# M_C_ext_esp32_cp2102.net
KiCad netlist of a schematic drawn in EAGLE
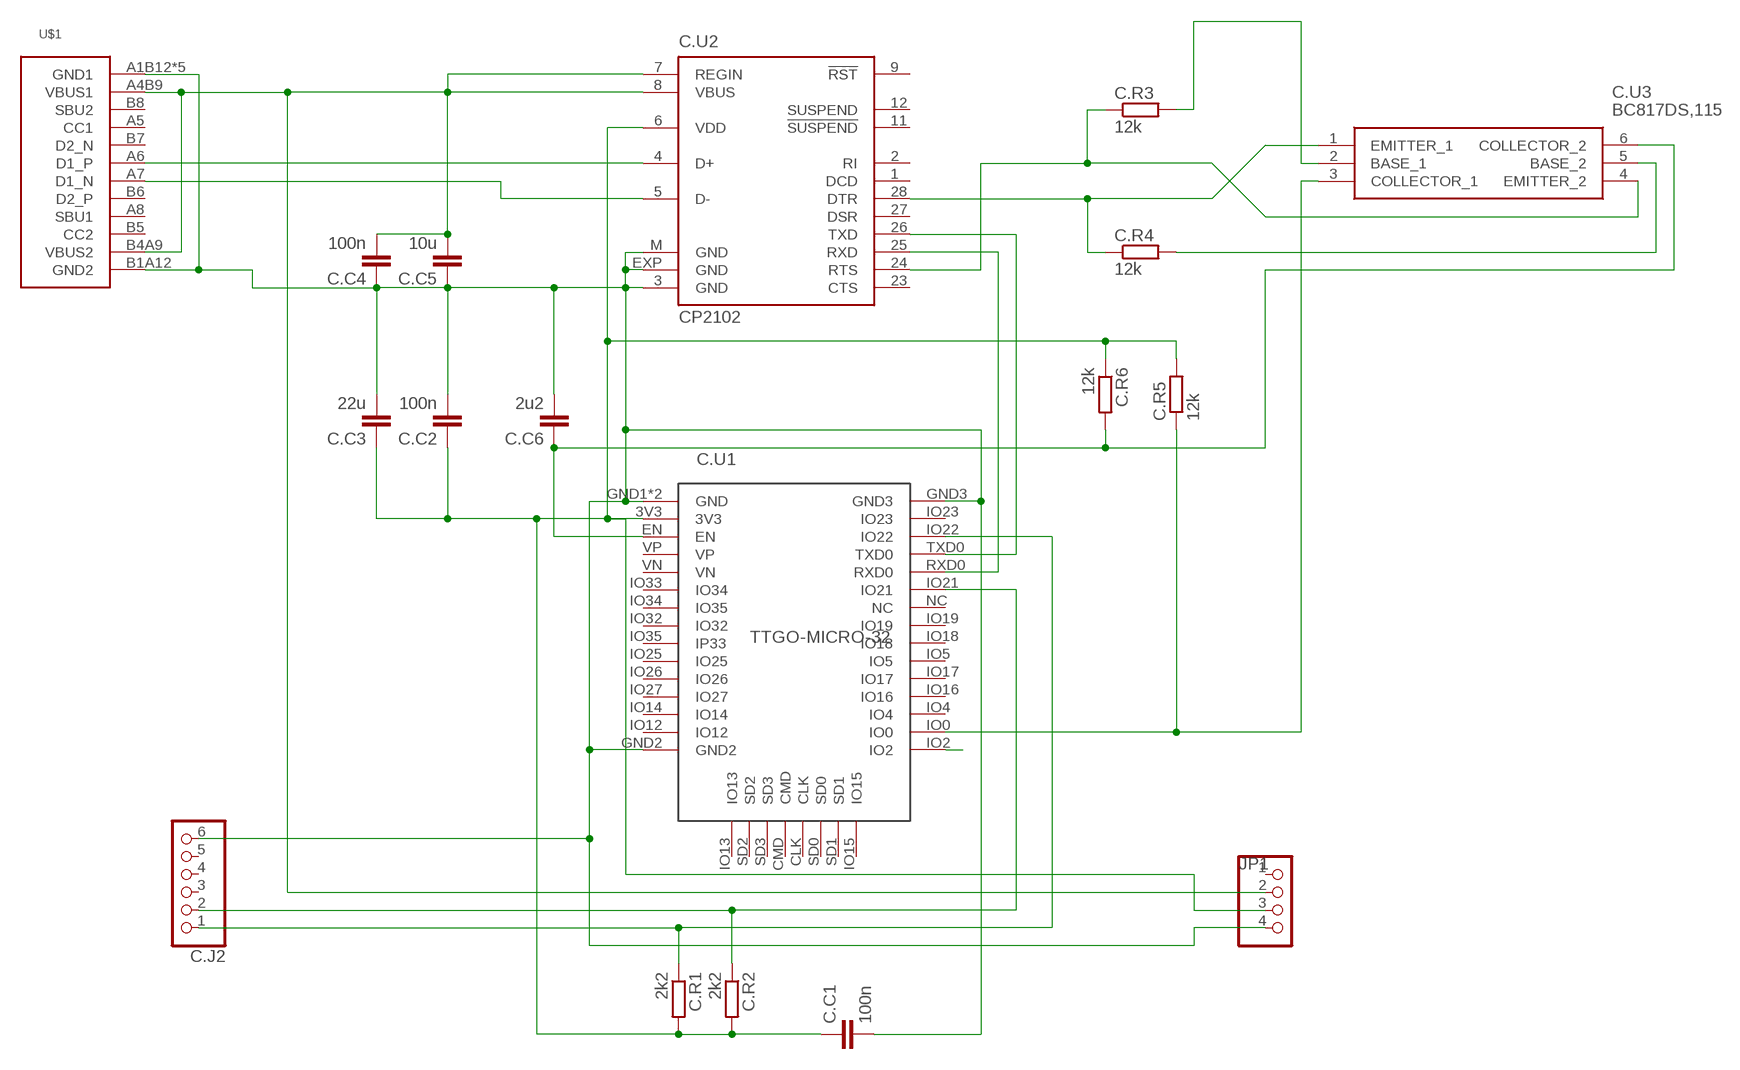
[diagram p0: schematic, sheet 1]

(export (version "E")
  (design (tool "Eeschema 10.0.6"))
  (components
    (comp (ref "C.C1")
      (value "100n")
      (footprint "eagle-import:C0603")
      (libsource (lib "eagle-import") (part "C-EUC0603"))
    )
    (comp (ref "C.C2")
      (value "100n")
      (footprint "eagle-import:C0603")
      (libsource (lib "eagle-import") (part "C-EUC0603"))
    )
    (comp (ref "C.C3")
      (value "22u")
      (footprint "eagle-import:C0805")
      (libsource (lib "eagle-import") (part "C-EUC0805"))
    )
    (comp (ref "C.C4")
      (value "100n")
      (footprint "eagle-import:C0603")
      (libsource (lib "eagle-import") (part "C-EUC0603"))
    )
    (comp (ref "C.C5")
      (value "10u")
      (footprint "eagle-import:C0603")
      (libsource (lib "eagle-import") (part "C-EUC0603"))
    )
    (comp (ref "C.C6")
      (value "2u2")
      (footprint "eagle-import:C0603")
      (libsource (lib "eagle-import") (part "C-EUC0603"))
    )
    (comp (ref "C.J2")
      (value "PINHD-1X6")
      (footprint "eagle-import:1X06")
      (libsource (lib "eagle-import") (part "PINHD-1X6"))
    )
    (comp (ref "C.R1")
      (value "2k2")
      (footprint "eagle-import:R0603")
      (libsource (lib "eagle-import") (part "R-EU_R0603"))
    )
    (comp (ref "C.R2")
      (value "2k2")
      (footprint "eagle-import:R0603")
      (libsource (lib "eagle-import") (part "R-EU_R0603"))
    )
    (comp (ref "C.R3")
      (value "12k")
      (footprint "eagle-import:R0603")
      (libsource (lib "eagle-import") (part "R-EU_R0603"))
    )
    (comp (ref "C.R4")
      (value "12k")
      (footprint "eagle-import:R0603")
      (libsource (lib "eagle-import") (part "R-EU_R0603"))
    )
    (comp (ref "C.R5")
      (value "12k")
      (footprint "eagle-import:R0603")
      (libsource (lib "eagle-import") (part "R-EU_R0603"))
    )
    (comp (ref "C.R6")
      (value "12k")
      (footprint "eagle-import:R0603")
      (libsource (lib "eagle-import") (part "R-EU_R0603"))
    )
    (comp (ref "C.U1")
      (value "TTGO-MICRO-32")
      (footprint "eagle-import:TTGO-MICRO-32")
      (libsource (lib "eagle-import") (part "TTGO-MICRO-32"))
    )
    (comp (ref "C.U2")
      (value "CP2102")
      (footprint "eagle-import:MLP28")
      (fields (field (name "MF") "FARNELL") (field (name "MPN") "CP2102-GM"))
      (libsource (lib "eagle-import") (part "CP2102"))
    )
    (comp (ref "C.U3")
      (value "BC817DS,115")
      (footprint "eagle-import:SOT95P275X110-6N")
      (fields (field (name "MOUSER_PART_NUMBER") "771-BC817DS115"))
      (libsource (lib "eagle-import") (part "BC817DS,115"))
    )
    (comp (ref "JP1")
      (value "PINHD-1X4")
      (footprint "eagle-import:1X04")
      (libsource (lib "eagle-import") (part "PINHD-1X4"))
    )
    (comp (ref "U$1")
      (value "USB-C")
      (footprint "eagle-import:USB-C")
      (libsource (lib "eagle-import") (part "USB-C"))
    )
  )
  (nets
    (net (code "1") (name "Net-(C.J2-Pad1)") (class "Default")
      (node (ref "C.J2") (pin "1") (pinfunction "1_1") (pintype "passive"))
      (node (ref "C.R1") (pin "1") (pinfunction "1_1") (pintype "passive"))
      (node (ref "C.U1") (pin "IO22") (pinfunction "IO22_IO22") (pintype "bidirectional"))
    )
    (net (code "2") (name "Net-(C.J2-Pad2)") (class "Default")
      (node (ref "C.J2") (pin "2") (pinfunction "2_2") (pintype "passive"))
      (node (ref "C.R2") (pin "1") (pinfunction "1_1") (pintype "passive"))
      (node (ref "C.U1") (pin "IO21") (pinfunction "IO21_IO21") (pintype "bidirectional"))
    )
    (net (code "3") (name "Net-(C.U2-D+)") (class "Default")
      (node (ref "C.U2") (pin "4") (pinfunction "D+_4") (pintype "bidirectional"))
      (node (ref "U$1") (pin "A6") (pinfunction "D1_P_A6") (pintype "bidirectional"))
    )
    (net (code "4") (name "Net-(C.U2-D-)") (class "Default")
      (node (ref "C.U2") (pin "5") (pinfunction "D-_5") (pintype "bidirectional"))
      (node (ref "U$1") (pin "A7") (pinfunction "D1_N_A7") (pintype "bidirectional"))
    )
    (net (code "5") (name "Net-(C.U2-DTR)") (class "Default")
      (node (ref "C.R4") (pin "1") (pinfunction "1_1") (pintype "passive"))
      (node (ref "C.U2") (pin "28") (pinfunction "DTR_28") (pintype "output"))
      (node (ref "C.U3") (pin "1") (pinfunction "EMITTER_1_1") (pintype "bidirectional"))
    )
    (net (code "6") (name "Net-(C.U2-REGIN)") (class "Default")
      (node (ref "C.C4") (pin "2") (pinfunction "2_2") (pintype "passive"))
      (node (ref "C.C5") (pin "2") (pinfunction "2_2") (pintype "passive"))
      (node (ref "C.U2") (pin "7") (pinfunction "REGIN_7") (pintype "passive"))
      (node (ref "C.U2") (pin "8") (pinfunction "VBUS_8") (pintype "input"))
      (node (ref "JP1") (pin "2") (pinfunction "2_2") (pintype "passive"))
      (node (ref "U$1") (pin "A4B9") (pinfunction "VBUS1_A4B9") (pintype "bidirectional"))
      (node (ref "U$1") (pin "B4A9") (pinfunction "VBUS2_B4A9") (pintype "bidirectional"))
    )
    (net (code "7") (name "Net-(C.U2-RTS)") (class "Default")
      (node (ref "C.R3") (pin "1") (pinfunction "1_1") (pintype "passive"))
      (node (ref "C.U2") (pin "24") (pinfunction "RTS_24") (pintype "output"))
      (node (ref "C.U3") (pin "4") (pinfunction "EMITTER_2_4") (pintype "bidirectional"))
    )
    (net (code "8") (name "Net-(C.U2-RXD)") (class "Default")
      (node (ref "C.U1") (pin "RXD0") (pinfunction "RXD0_RXD0") (pintype "bidirectional"))
      (node (ref "C.U2") (pin "25") (pinfunction "RXD_25") (pintype "input"))
    )
    (net (code "9") (name "Net-(C.U2-TXD)") (class "Default")
      (node (ref "C.U1") (pin "TXD0") (pinfunction "TXD0_TXD0") (pintype "bidirectional"))
      (node (ref "C.U2") (pin "26") (pinfunction "TXD_26") (pintype "output"))
    )
    (net (code "10") (name "Net-(C.U2-VDD)") (class "Default")
      (node (ref "C.C1") (pin "1") (pinfunction "1_1") (pintype "passive"))
      (node (ref "C.C2") (pin "1") (pinfunction "1_1") (pintype "passive"))
      (node (ref "C.C3") (pin "1") (pinfunction "1_1") (pintype "passive"))
      (node (ref "C.R1") (pin "2") (pinfunction "2_2") (pintype "passive"))
      (node (ref "C.R2") (pin "2") (pinfunction "2_2") (pintype "passive"))
      (node (ref "C.R5") (pin "2") (pinfunction "2_2") (pintype "passive"))
      (node (ref "C.R6") (pin "1") (pinfunction "1_1") (pintype "passive"))
      (node (ref "C.U1") (pin "3V3") (pinfunction "3V3_3V3") (pintype "power_in"))
      (node (ref "C.U2") (pin "6") (pinfunction "VDD_6") (pintype "power_in"))
      (node (ref "JP1") (pin "3") (pinfunction "3_3") (pintype "passive"))
    )
    (net (code "11") (name "Net-(C.U3-BASE_1)") (class "Default")
      (node (ref "C.R3") (pin "2") (pinfunction "2_2") (pintype "passive"))
      (node (ref "C.U3") (pin "2") (pinfunction "BASE_1_2") (pintype "bidirectional"))
    )
    (net (code "12") (name "Net-(C.U3-BASE_2)") (class "Default")
      (node (ref "C.R4") (pin "2") (pinfunction "2_2") (pintype "passive"))
      (node (ref "C.U3") (pin "5") (pinfunction "BASE_2_5") (pintype "bidirectional"))
    )
    (net (code "13") (name "Net-(C.U3-COLLECTOR_1)") (class "Default")
      (node (ref "C.R5") (pin "1") (pinfunction "1_1") (pintype "passive"))
      (node (ref "C.U1") (pin "IO0") (pinfunction "IO0_IO0") (pintype "bidirectional"))
      (node (ref "C.U3") (pin "3") (pinfunction "COLLECTOR_1_3") (pintype "bidirectional"))
    )
    (net (code "14") (name "Net-(C.U3-COLLECTOR_2)") (class "Default")
      (node (ref "C.C6") (pin "1") (pinfunction "1_1") (pintype "passive"))
      (node (ref "C.R6") (pin "2") (pinfunction "2_2") (pintype "passive"))
      (node (ref "C.U1") (pin "EN") (pinfunction "EN_EN") (pintype "bidirectional"))
      (node (ref "C.U3") (pin "6") (pinfunction "COLLECTOR_2_6") (pintype "bidirectional"))
    )
    (net (code "15") (name "Net-(U$1-GND2)") (class "Default")
      (node (ref "C.C1") (pin "2") (pinfunction "2_2") (pintype "passive"))
      (node (ref "C.C2") (pin "2") (pinfunction "2_2") (pintype "passive"))
      (node (ref "C.C3") (pin "2") (pinfunction "2_2") (pintype "passive"))
      (node (ref "C.C4") (pin "1") (pinfunction "1_1") (pintype "passive"))
      (node (ref "C.C5") (pin "1") (pinfunction "1_1") (pintype "passive"))
      (node (ref "C.C6") (pin "2") (pinfunction "2_2") (pintype "passive"))
      (node (ref "C.J2") (pin "6") (pinfunction "6_6") (pintype "passive"))
      (node (ref "C.U1") (pin "GND1") (pinfunction "GND_GND1") (pintype "power_in"))
      (node (ref "C.U1") (pin "GND2") (pinfunction "GND2_GND2") (pintype "power_in"))
      (node (ref "C.U1") (pin "GND3") (pinfunction "GND3_GND3") (pintype "power_in"))
      (node (ref "C.U1") (pin "GND4") (pinfunction "GND_GND4") (pintype "power_in"))
      (node (ref "C.U2") (pin "3") (pinfunction "GND_3") (pintype "power_in"))
      (node (ref "C.U2") (pin "EXP") (pinfunction "GND_EXP") (pintype "power_in"))
      (node (ref "C.U2") (pin "M") (pinfunction "GND_M") (pintype "power_in"))
      (node (ref "JP1") (pin "4") (pinfunction "4_4") (pintype "passive"))
      (node (ref "U$1") (pin "A1B12") (pinfunction "GND1_A1B12") (pintype "bidirectional"))
      (node (ref "U$1") (pin "B1A12") (pinfunction "GND2_B1A12") (pintype "bidirectional"))
      (node (ref "U$1") (pin "SH1") (pinfunction "GND1_SH1") (pintype "bidirectional"))
      (node (ref "U$1") (pin "SH2") (pinfunction "GND1_SH2") (pintype "bidirectional"))
      (node (ref "U$1") (pin "SH3") (pinfunction "GND1_SH3") (pintype "bidirectional"))
      (node (ref "U$1") (pin "SH4") (pinfunction "GND1_SH4") (pintype "bidirectional"))
    )
    (net (code "16") (name "unconnected-(C.J2-Pad3)") (class "Default")
      (node (ref "C.J2") (pin "3") (pinfunction "3_3") (pintype "passive"))
    )
    (net (code "17") (name "unconnected-(C.J2-Pad4)") (class "Default")
      (node (ref "C.J2") (pin "4") (pinfunction "4_4") (pintype "passive"))
    )
    (net (code "18") (name "unconnected-(C.J2-Pad5)") (class "Default")
      (node (ref "C.J2") (pin "5") (pinfunction "5_5") (pintype "passive"))
    )
    (net (code "19") (name "unconnected-(C.U1-IO34-PadIO33)") (class "Default")
      (node (ref "C.U1") (pin "IO33") (pinfunction "IO34_IO33") (pintype "bidirectional"))
    )
    (net (code "20") (name "unconnected-(C.U1-IO35-PadIO34)") (class "Default")
      (node (ref "C.U1") (pin "IO34") (pinfunction "IO35_IO34") (pintype "bidirectional"))
    )
    (net (code "21") (name "unconnected-(C.U1-IP33-PadIO35)") (class "Default")
      (node (ref "C.U1") (pin "IO35") (pinfunction "IP33_IO35") (pintype "bidirectional"))
    )
    (net (code "22") (name "unconnected-(C.U1-PadCLK)") (class "Default")
      (node (ref "C.U1") (pin "CLK") (pinfunction "CLK_CLK") (pintype "bidirectional"))
    )
    (net (code "23") (name "unconnected-(C.U1-PadCMD)") (class "Default")
      (node (ref "C.U1") (pin "CMD") (pinfunction "CMD_CMD") (pintype "bidirectional"))
    )
    (net (code "24") (name "unconnected-(C.U1-PadIO2)") (class "Default")
      (node (ref "C.U1") (pin "IO2") (pinfunction "IO2_IO2") (pintype "bidirectional"))
    )
    (net (code "25") (name "unconnected-(C.U1-PadIO4)") (class "Default")
      (node (ref "C.U1") (pin "IO4") (pinfunction "IO4_IO4") (pintype "bidirectional"))
    )
    (net (code "26") (name "unconnected-(C.U1-PadIO5)") (class "Default")
      (node (ref "C.U1") (pin "IO5") (pinfunction "IO5_IO5") (pintype "bidirectional"))
    )
    (net (code "27") (name "unconnected-(C.U1-PadIO12)") (class "Default")
      (node (ref "C.U1") (pin "IO12") (pinfunction "IO12_IO12") (pintype "bidirectional"))
    )
    (net (code "28") (name "unconnected-(C.U1-PadIO13)") (class "Default")
      (node (ref "C.U1") (pin "IO13") (pinfunction "IO13_IO13") (pintype "bidirectional"))
    )
    (net (code "29") (name "unconnected-(C.U1-PadIO14)") (class "Default")
      (node (ref "C.U1") (pin "IO14") (pinfunction "IO14_IO14") (pintype "bidirectional"))
    )
    (net (code "30") (name "unconnected-(C.U1-PadIO15)") (class "Default")
      (node (ref "C.U1") (pin "IO15") (pinfunction "IO15_IO15") (pintype "bidirectional"))
    )
    (net (code "31") (name "unconnected-(C.U1-PadIO16)") (class "Default")
      (node (ref "C.U1") (pin "IO16") (pinfunction "IO16_IO16") (pintype "bidirectional"))
    )
    (net (code "32") (name "unconnected-(C.U1-PadIO17)") (class "Default")
      (node (ref "C.U1") (pin "IO17") (pinfunction "IO17_IO17") (pintype "bidirectional"))
    )
    (net (code "33") (name "unconnected-(C.U1-PadIO18)") (class "Default")
      (node (ref "C.U1") (pin "IO18") (pinfunction "IO18_IO18") (pintype "bidirectional"))
    )
    (net (code "34") (name "unconnected-(C.U1-PadIO19)") (class "Default")
      (node (ref "C.U1") (pin "IO19") (pinfunction "IO19_IO19") (pintype "bidirectional"))
    )
    (net (code "35") (name "unconnected-(C.U1-PadIO23)") (class "Default")
      (node (ref "C.U1") (pin "IO23") (pinfunction "IO23_IO23") (pintype "bidirectional"))
    )
    (net (code "36") (name "unconnected-(C.U1-PadIO25)") (class "Default")
      (node (ref "C.U1") (pin "IO25") (pinfunction "IO25_IO25") (pintype "bidirectional"))
    )
    (net (code "37") (name "unconnected-(C.U1-PadIO26)") (class "Default")
      (node (ref "C.U1") (pin "IO26") (pinfunction "IO26_IO26") (pintype "bidirectional"))
    )
    (net (code "38") (name "unconnected-(C.U1-PadIO27)") (class "Default")
      (node (ref "C.U1") (pin "IO27") (pinfunction "IO27_IO27") (pintype "bidirectional"))
    )
    (net (code "39") (name "unconnected-(C.U1-PadIO32)") (class "Default")
      (node (ref "C.U1") (pin "IO32") (pinfunction "IO32_IO32") (pintype "bidirectional"))
    )
    (net (code "40") (name "unconnected-(C.U1-PadNC)") (class "Default")
      (node (ref "C.U1") (pin "NC") (pinfunction "NC_NC") (pintype "no_connect"))
    )
    (net (code "41") (name "unconnected-(C.U1-PadSD0)") (class "Default")
      (node (ref "C.U1") (pin "SD0") (pinfunction "SD0_SD0") (pintype "bidirectional"))
    )
    (net (code "42") (name "unconnected-(C.U1-PadSD1)") (class "Default")
      (node (ref "C.U1") (pin "SD1") (pinfunction "SD1_SD1") (pintype "bidirectional"))
    )
    (net (code "43") (name "unconnected-(C.U1-PadSD2)") (class "Default")
      (node (ref "C.U1") (pin "SD2") (pinfunction "SD2_SD2") (pintype "bidirectional"))
    )
    (net (code "44") (name "unconnected-(C.U1-PadSD3)") (class "Default")
      (node (ref "C.U1") (pin "SD3") (pinfunction "SD3_SD3") (pintype "bidirectional"))
    )
    (net (code "45") (name "unconnected-(C.U1-PadVN)") (class "Default")
      (node (ref "C.U1") (pin "VN") (pinfunction "VN_VN") (pintype "bidirectional"))
    )
    (net (code "46") (name "unconnected-(C.U1-PadVP)") (class "Default")
      (node (ref "C.U1") (pin "VP") (pinfunction "VP_VP") (pintype "bidirectional"))
    )
    (net (code "47") (name "unconnected-(C.U2-CTS-Pad23)") (class "Default")
      (node (ref "C.U2") (pin "23") (pinfunction "CTS_23") (pintype "input"))
    )
    (net (code "48") (name "unconnected-(C.U2-DCD-Pad1)") (class "Default")
      (node (ref "C.U2") (pin "1") (pinfunction "DCD_1") (pintype "input"))
    )
    (net (code "49") (name "unconnected-(C.U2-DSR-Pad27)") (class "Default")
      (node (ref "C.U2") (pin "27") (pinfunction "DSR_27") (pintype "input"))
    )
    (net (code "50") (name "unconnected-(C.U2-RI-Pad2)") (class "Default")
      (node (ref "C.U2") (pin "2") (pinfunction "RI_2") (pintype "input"))
    )
    (net (code "51") (name "unconnected-(C.U2-SUSPEND-Pad12)") (class "Default")
      (node (ref "C.U2") (pin "12") (pinfunction "SUSPEND_12") (pintype "output"))
    )
    (net (code "52") (name "unconnected-(C.U2-~{RST}-Pad9)") (class "Default")
      (node (ref "C.U2") (pin "9") (pinfunction "~{RST}_9") (pintype "bidirectional"))
    )
    (net (code "53") (name "unconnected-(C.U2-~{SUSPEND}-Pad11)") (class "Default")
      (node (ref "C.U2") (pin "11") (pinfunction "~{SUSPEND}_11") (pintype "output"))
    )
    (net (code "54") (name "unconnected-(JP1-Pad1)") (class "Default")
      (node (ref "JP1") (pin "1") (pinfunction "1_1") (pintype "passive"))
    )
    (net (code "55") (name "unconnected-(U$1-CC1-PadA5)") (class "Default")
      (node (ref "U$1") (pin "A5") (pinfunction "CC1_A5") (pintype "bidirectional"))
    )
    (net (code "56") (name "unconnected-(U$1-CC2-PadB5)") (class "Default")
      (node (ref "U$1") (pin "B5") (pinfunction "CC2_B5") (pintype "bidirectional"))
    )
    (net (code "57") (name "unconnected-(U$1-D2_N-PadB7)") (class "Default")
      (node (ref "U$1") (pin "B7") (pinfunction "D2_N_B7") (pintype "bidirectional"))
    )
    (net (code "58") (name "unconnected-(U$1-D2_P-PadB6)") (class "Default")
      (node (ref "U$1") (pin "B6") (pinfunction "D2_P_B6") (pintype "bidirectional"))
    )
    (net (code "59") (name "unconnected-(U$1-SBU1-PadA8)") (class "Default")
      (node (ref "U$1") (pin "A8") (pinfunction "SBU1_A8") (pintype "bidirectional"))
    )
    (net (code "60") (name "unconnected-(U$1-SBU2-PadB8)") (class "Default")
      (node (ref "U$1") (pin "B8") (pinfunction "SBU2_B8") (pintype "bidirectional"))
    )
  )
)
